# clock_module.net
KiCad netlist of a schematic drawn in Altium Designer
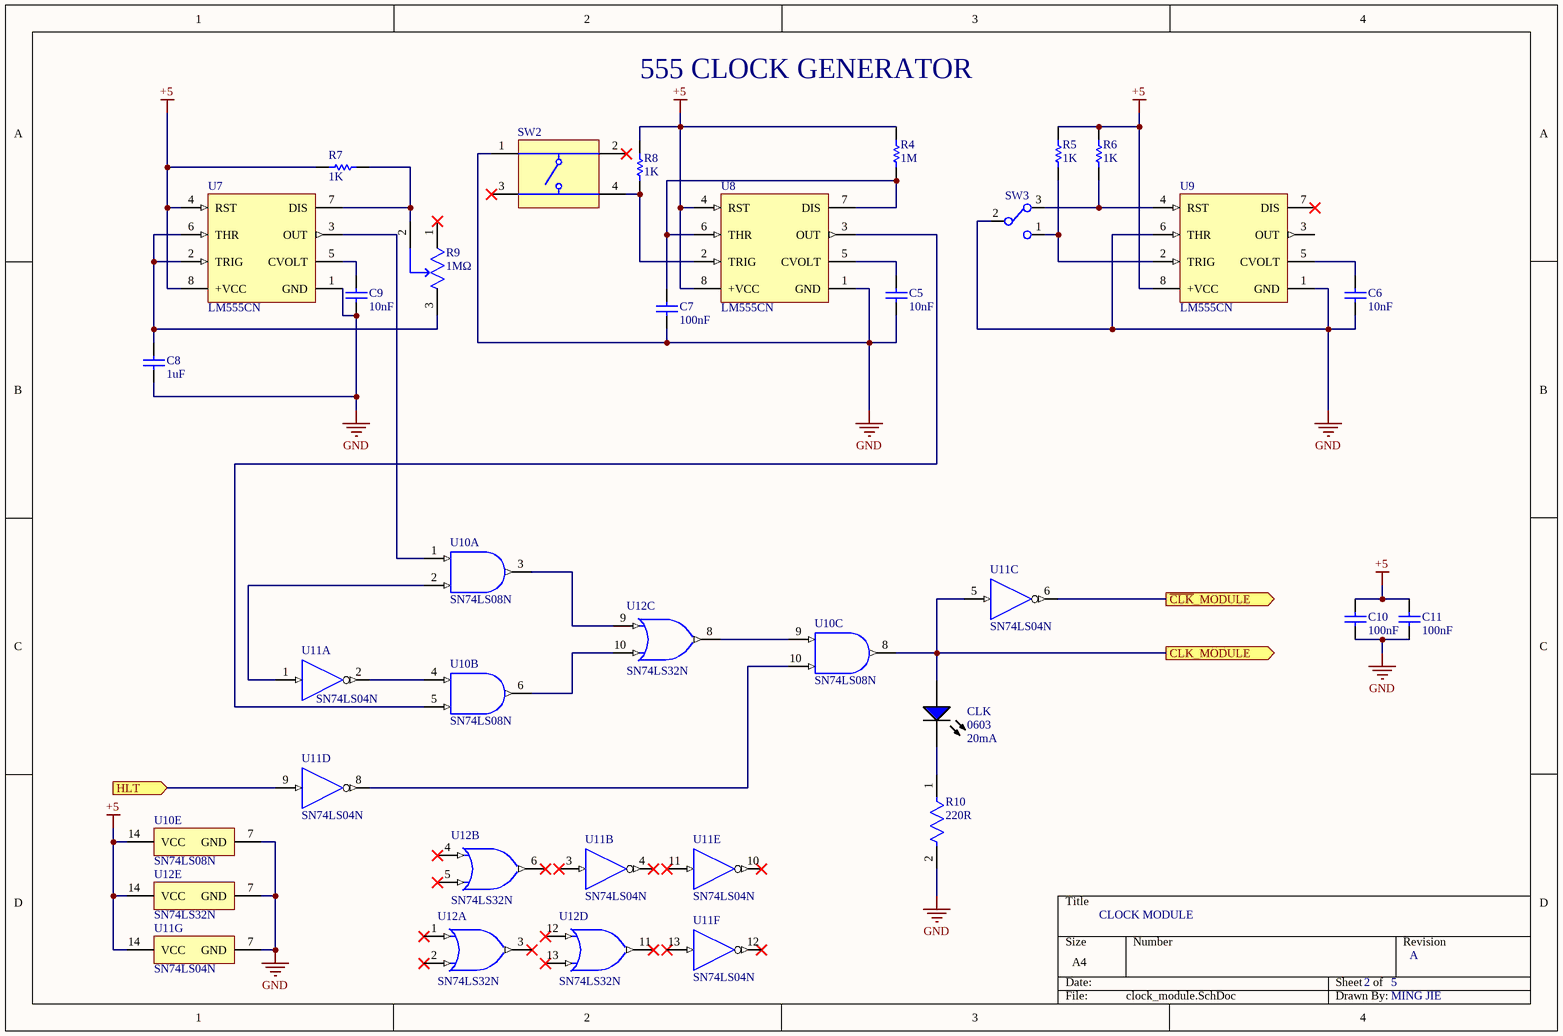
[diagram p0: clock_module.SchDoc]

(export (version "E")
  (design (tool "Eeschema 10.0.6"))
  (components
    (comp (ref "C5")
      (value "GRM216R71H103KA01D")
      (footprint "CAPC2013X70X45ML10T25")
      (description "Chip Capacitor, 10 nF, +/- 10%, 50 V, -55 to 125 degC, 0805 (2012 Metric), RoHS, Tape and Reel")
      (fields
        (field (name "CAPACITANCE") "10nF")
        (field (name "TOLERANCE") "10%")
        (field (name "MANUFACTURER") "Murata")
      )
      (libsource (lib "Altium Content Vault") (part "CAP-NP-2"))
    )
    (comp (ref "C6")
      (value "GRM216R71H103KA01D")
      (footprint "CAPC2013X70X45ML10T25")
      (description "Chip Capacitor, 10 nF, +/- 10%, 50 V, -55 to 125 degC, 0805 (2012 Metric), RoHS, Tape and Reel")
      (fields
        (field (name "CAPACITANCE") "10nF")
        (field (name "TOLERANCE") "10%")
        (field (name "MANUFACTURER") "Murata")
      )
      (libsource (lib "Altium Content Vault") (part "CAP-NP-2"))
    )
    (comp (ref "C7")
      (value "GRM21BR71H104KA01L")
      (footprint "CAPC2013X135X45ML10T25")
      (description "Chip Capacitor, 0.1 uF, +/- 10%, 50 V, -55 to 125 degC, 0805 (2012 Metric), RoHS, Tape and Reel")
      (fields
        (field (name "VOLTAGE") "50V")
        (field (name "CAPACITANCE") "100nF")
        (field (name "TOLERANCE") "10%")
      )
      (libsource (lib "Altium Content Vault") (part "CAP-NP-2"))
    )
    (comp (ref "C8")
      (value "GRM216R61E105KA12D")
      (footprint "CAPC2013X70X45NL10T25")
      (fields (field (name "MANUFACTURER") "Murata") (field (name "CAPACITANCE") "1uF"))
      (libsource (lib "Altium Content Vault") (part "CAP"))
    )
    (comp (ref "C9")
      (value "GRM216R71H103KA01D")
      (footprint "CAPC2013X70X45ML10T25")
      (description "Chip Capacitor, 10 nF, +/- 10%, 50 V, -55 to 125 degC, 0805 (2012 Metric), RoHS, Tape and Reel")
      (fields
        (field (name "CAPACITANCE") "10nF")
        (field (name "TOLERANCE") "10%")
        (field (name "MANUFACTURER") "Murata")
      )
      (libsource (lib "Altium Content Vault") (part "CAP-NP-2"))
    )
    (comp (ref "C10")
      (value "GRM21BR71H104KA01L")
      (footprint "CAPC2013X135X45ML10T25")
      (description "Chip Capacitor, 0.1 uF, +/- 10%, 50 V, -55 to 125 degC, 0805 (2012 Metric), RoHS, Tape and Reel")
      (fields
        (field (name "VOLTAGE") "50V")
        (field (name "CAPACITANCE") "100nF")
        (field (name "TOLERANCE") "10%")
      )
      (libsource (lib "Altium Content Vault") (part "CAP-NP-2"))
    )
    (comp (ref "C11")
      (value "GRM21BR71H104KA01L")
      (footprint "CAPC2013X135X45ML10T25")
      (description "Chip Capacitor, 0.1 uF, +/- 10%, 50 V, -55 to 125 degC, 0805 (2012 Metric), RoHS, Tape and Reel")
      (fields
        (field (name "VOLTAGE") "50V")
        (field (name "CAPACITANCE") "100nF")
        (field (name "TOLERANCE") "10%")
      )
      (libsource (lib "Altium Content Vault") (part "CAP-NP-2"))
    )
    (comp (ref "CLK")
      (value "19-217/BHC-ZL1M2RY/3T")
      (footprint "EVRL-0603-2_V")
      (description "Chip LED, Blue, 5 V, 25 mA, -40 to 85 degC, 2-Pin SMD (0603), RoHS, Tape and Reel")
      (fields
        (field (name "PACKAGE REFERENCE") "0603")
        (field (name "TEST CURRENT") "20mA")
        (field (name "MANUFACTURER") "Everlight Electronics")
      )
      (libsource (lib "Altium Content Vault") (part "LED-BLUE-AK-2"))
    )
    (comp (ref "R4")
      (value "CRCW08051M00JNEA")
      (footprint "RESC2013X50X30NL20T20")
      (fields (field (name "MANUFACTURER") "Vishay Dale") (field (name "RESISTANCE") "1M"))
      (libsource (lib "Altium Content Vault") (part "RES"))
    )
    (comp (ref "R5")
      (value "CRCW08051K00FKEA")
      (footprint "RESC2013X50X30NL20T20")
      (fields (field (name "MANUFACTURER") "Vishay Dale") (field (name "RESISTANCE") "1K"))
      (libsource (lib "Altium Content Vault") (part "RES"))
    )
    (comp (ref "R6")
      (value "CRCW08051K00FKEA")
      (footprint "RESC2013X50X30NL20T20")
      (fields (field (name "MANUFACTURER") "Vishay Dale") (field (name "RESISTANCE") "1K"))
      (libsource (lib "Altium Content Vault") (part "RES"))
    )
    (comp (ref "R7")
      (value "CRCW08051K00FKEA")
      (footprint "RESC2013X50X30NL20T20")
      (fields (field (name "MANUFACTURER") "Vishay Dale") (field (name "RESISTANCE") "1K"))
      (libsource (lib "Altium Content Vault") (part "RES"))
    )
    (comp (ref "R8")
      (value "CRCW08051K00FKEA")
      (footprint "RESC2013X50X30NL20T20")
      (fields (field (name "MANUFACTURER") "Vishay Dale") (field (name "RESISTANCE") "1K"))
      (libsource (lib "Altium Content Vault") (part "RES"))
    )
    (comp (ref "R9")
      (value "3296W-1-105LF")
      (footprint "FP-3296W-MFG")
      (description "TRIMMER 1M OHM 0.5W PC PIN TOP")
      (fields
        (field (name "MANUFACTURER") "Bourns")
        (field (name "RESISTANCE") "1MΩ")
        (field (name "OCTOPART") "https://octopart.com/3296w-1-504lf-bourns-143884")
      )
      (libsource (lib "Altium Content Vault") (part "8d460c8a6f7ec10b1759d1b9c49aa93"))
    )
    (comp (ref "R10")
      (value "CRCW0805220RFKEA")
      (footprint "FP-CRCW0805-e3-MFG")
      (description "RES Thick Film, 220Ω, 1%, 0.125W, 100ppm/°C, 0805")
      (fields (field (name "RESISTANCE") "220R") (field (name "TOLERANCE") "1%"))
      (libsource (lib "Altium Content Vault") (part "1029c3af85768c4190bb7ad29bc67b5"))
    )
    (comp (ref "SW2")
      (value "K2-1102SP-C4SC-04")
      (footprint "TECO-FSM4JSMA_V")
      (description "Swicth, SPST, 24 V, -35 to 85 degC, 4-Pin SMD, RoHS, Tape and Reel")
      (fields (field (name "MANUFACTURER") "TE Connectivity"))
      (libsource (lib "Altium Content Vault") (part "SW-SPST-4_A"))
    )
    (comp (ref "SW3")
      (value "SS-12D02-VG4")
      (footprint "5_2-54mm_SPDT")
      (description "SPDT, Korean Hroparts Elec SS-12D02-VG4")
      (libsource (lib "6502_lib") (part "SS-12D02-VG4"))
    )
    (comp (ref "U7")
      (value "LM555CN")
      (footprint "N08E")
      (description "Timer, 8-pin MDIP")
      (fields (field (name "MANUFACTURER") "National Semiconductor"))
      (libsource (lib "Altium Content Vault") (part "AN-TIMER-LM555-8"))
    )
    (comp (ref "U8")
      (value "LM555CN")
      (footprint "N08E")
      (description "Timer, 8-pin MDIP")
      (fields (field (name "MANUFACTURER") "National Semiconductor"))
      (libsource (lib "Altium Content Vault") (part "AN-TIMER-LM555-8"))
    )
    (comp (ref "U9")
      (value "LM555CN")
      (footprint "N08E")
      (description "Timer, 8-pin MDIP")
      (fields (field (name "MANUFACTURER") "National Semiconductor"))
      (libsource (lib "Altium Content Vault") (part "AN-TIMER-LM555-8"))
    )
    (comp (ref "U10")
      (value "SN74LS08N")
      (footprint "N0014A")
      (description "Quadruple 2-Input Positive-AND Gates, N0014A, TUBE")
      (fields
        (field (name "MANUFACTURER") "Texas Instruments")
        (field (name "GENERIC PART NUMBER") "SN74LS08")
      )
      (libsource (lib "Altium Content Vault") (part "TI-AND-4-2IN-14"))
    )
    (comp (ref "U11")
      (value "SN74LS04N")
      (footprint "N0014A")
      (description "Hex inverters, N0014A, TUBE")
      (fields
        (field (name "MANUFACTURER") "Texas Instruments")
        (field (name "GENERIC PART NUMBER") "SN74LS04")
      )
      (libsource (lib "Altium Content Vault") (part "TI-CD_SNX4XXXXXX4X_19A-14"))
    )
    (comp (ref "U12")
      (value "SN74LS32N")
      (footprint "N0014A")
      (description "Quad 2-input positive-OR gates, N0014A, TUBE")
      (fields
        (field (name "GENERIC PART NUMBER") "SN74LS32")
        (field (name "MANUFACTURER") "Texas Instruments")
      )
      (libsource (lib "Altium Content Vault") (part "TI-OR-4-2IN-14"))
    )
  )
  (nets
    (net (code "1") (name "+5") (class "Default")
      (node (ref "C10") (pin "1") (pinfunction "1_1") (pintype "passive"))
      (node (ref "C11") (pin "1") (pinfunction "1_1") (pintype "passive"))
      (node (ref "R4") (pin "1") (pinfunction "1_1") (pintype "passive"))
      (node (ref "R5") (pin "2") (pinfunction "2_2") (pintype "passive"))
      (node (ref "R6") (pin "2") (pinfunction "2_2") (pintype "passive"))
      (node (ref "R7") (pin "1") (pinfunction "1_1") (pintype "passive"))
      (node (ref "R8") (pin "2") (pinfunction "2_2") (pintype "passive"))
      (node (ref "U10") (pin "14") (pinfunction "VCC_14") (pintype "power_in"))
      (node (ref "U11") (pin "14") (pinfunction "VCC_14") (pintype "power_in"))
      (node (ref "U12") (pin "14") (pinfunction "VCC_14") (pintype "power_in"))
      (node (ref "U7") (pin "4") (pinfunction "RST_4") (pintype "input"))
      (node (ref "U7") (pin "8") (pinfunction "+VCC_8") (pintype "power_in"))
      (node (ref "U8") (pin "4") (pinfunction "RST_4") (pintype "input"))
      (node (ref "U8") (pin "8") (pinfunction "+VCC_8") (pintype "power_in"))
      (node (ref "U9") (pin "8") (pinfunction "+VCC_8") (pintype "power_in"))
    )
    (net (code "2") (name "/CLK_MODULE") (class "Default")
      (node (ref "CLK") (pin "1") (pinfunction "A_1") (pintype "passive"))
      (node (ref "U10") (pin "8") (pinfunction "3Y_8") (pintype "output"))
      (node (ref "U11") (pin "5") (pinfunction "3A_5") (pintype "input"))
    )
    (net (code "3") (name "/HLT") (class "Default")
      (node (ref "U11") (pin "9") (pinfunction "4A_9") (pintype "input"))
    )
    (net (code "4") (name "/~{CLK}_MODULE") (class "Default")
      (node (ref "U11") (pin "6") (pinfunction "~{3Y}_6") (pintype "output"))
    )
    (net (code "5") (name "GND") (class "Default")
      (node (ref "C10") (pin "2") (pinfunction "2_2") (pintype "passive"))
      (node (ref "C11") (pin "2") (pinfunction "2_2") (pintype "passive"))
      (node (ref "C5") (pin "1") (pinfunction "1_1") (pintype "passive"))
      (node (ref "C6") (pin "1") (pinfunction "1_1") (pintype "passive"))
      (node (ref "C7") (pin "2") (pinfunction "2_2") (pintype "passive"))
      (node (ref "C8") (pin "2") (pinfunction "2_2") (pintype "passive"))
      (node (ref "C9") (pin "1") (pinfunction "1_1") (pintype "passive"))
      (node (ref "R10") (pin "2") (pinfunction "2_2") (pintype "passive"))
      (node (ref "SW2") (pin "1") (pinfunction "1_1") (pintype "passive"))
      (node (ref "SW3") (pin "2") (pinfunction "2_2") (pintype "passive"))
      (node (ref "U10") (pin "7") (pinfunction "GND_7") (pintype "power_in"))
      (node (ref "U11") (pin "7") (pinfunction "GND_7") (pintype "power_in"))
      (node (ref "U12") (pin "7") (pinfunction "GND_7") (pintype "power_in"))
      (node (ref "U7") (pin "1") (pinfunction "GND_1") (pintype "power_in"))
      (node (ref "U8") (pin "1") (pinfunction "GND_1") (pintype "power_in"))
      (node (ref "U9") (pin "1") (pinfunction "GND_1") (pintype "power_in"))
      (node (ref "U9") (pin "6") (pinfunction "THR_6") (pintype "input"))
    )
    (net (code "6") (name "Net-(CLK-K)") (class "Default")
      (node (ref "CLK") (pin "2") (pinfunction "K_2") (pintype "passive"))
      (node (ref "R10") (pin "1") (pinfunction "1_1") (pintype "passive"))
    )
    (net (code "7") (name "Net-(R9-CW)") (class "Default")
      (node (ref "C8") (pin "1") (pinfunction "1_1") (pintype "passive"))
      (node (ref "R9") (pin "3") (pinfunction "CW_3") (pintype "passive"))
      (node (ref "U7") (pin "2") (pinfunction "TRIG_2") (pintype "input"))
      (node (ref "U7") (pin "6") (pinfunction "THR_6") (pintype "input"))
    )
    (net (code "8") (name "Net-(R9-WIPER)") (class "Default")
      (node (ref "R7") (pin "2") (pinfunction "2_2") (pintype "passive"))
      (node (ref "R9") (pin "2") (pinfunction "WIPER_2") (pintype "passive"))
      (node (ref "U7") (pin "7") (pinfunction "DIS_7") (pintype "open_collector"))
    )
    (net (code "9") (name "Net-(U7-CVOLT)") (class "Default")
      (node (ref "C9") (pin "2") (pinfunction "2_2") (pintype "passive"))
      (node (ref "U7") (pin "5") (pinfunction "CVOLT_5") (pintype "passive"))
    )
    (net (code "10") (name "Net-(U8-CVOLT)") (class "Default")
      (node (ref "C5") (pin "2") (pinfunction "2_2") (pintype "passive"))
      (node (ref "U8") (pin "5") (pinfunction "CVOLT_5") (pintype "passive"))
    )
    (net (code "11") (name "Net-(U8-DIS)") (class "Default")
      (node (ref "C7") (pin "1") (pinfunction "1_1") (pintype "passive"))
      (node (ref "R4") (pin "2") (pinfunction "2_2") (pintype "passive"))
      (node (ref "U8") (pin "6") (pinfunction "THR_6") (pintype "input"))
      (node (ref "U8") (pin "7") (pinfunction "DIS_7") (pintype "open_collector"))
    )
    (net (code "12") (name "Net-(U8-TRIG)") (class "Default")
      (node (ref "R8") (pin "1") (pinfunction "1_1") (pintype "passive"))
      (node (ref "SW2") (pin "4") (pinfunction "4_4") (pintype "passive"))
      (node (ref "U8") (pin "2") (pinfunction "TRIG_2") (pintype "input"))
    )
    (net (code "13") (name "Net-(U9-CVOLT)") (class "Default")
      (node (ref "C6") (pin "2") (pinfunction "2_2") (pintype "passive"))
      (node (ref "U9") (pin "5") (pinfunction "CVOLT_5") (pintype "passive"))
    )
    (net (code "14") (name "Net-(U9-RST)") (class "Default")
      (node (ref "R6") (pin "1") (pinfunction "1_1") (pintype "passive"))
      (node (ref "SW3") (pin "3") (pinfunction "3_3") (pintype "passive"))
      (node (ref "U9") (pin "4") (pinfunction "RST_4") (pintype "input"))
    )
    (net (code "15") (name "Net-(U9-TRIG)") (class "Default")
      (node (ref "R5") (pin "1") (pinfunction "1_1") (pintype "passive"))
      (node (ref "SW3") (pin "1") (pinfunction "1_1") (pintype "passive"))
      (node (ref "U9") (pin "2") (pinfunction "TRIG_2") (pintype "input"))
    )
    (net (code "16") (name "Net-(U10A-1A)") (class "Default")
      (node (ref "U10") (pin "1") (pinfunction "1A_1") (pintype "input"))
      (node (ref "U7") (pin "3") (pinfunction "OUT_3") (pintype "output"))
    )
    (net (code "17") (name "Net-(U10A-1B)") (class "Default")
      (node (ref "U10") (pin "2") (pinfunction "1B_2") (pintype "input"))
      (node (ref "U11") (pin "1") (pinfunction "1A_1") (pintype "input"))
    )
    (net (code "18") (name "Net-(U10A-1Y)") (class "Default")
      (node (ref "U10") (pin "3") (pinfunction "1Y_3") (pintype "output"))
      (node (ref "U12") (pin "9") (pinfunction "3A_9") (pintype "input"))
    )
    (net (code "19") (name "Net-(U10B-2A)") (class "Default")
      (node (ref "U10") (pin "4") (pinfunction "2A_4") (pintype "input"))
      (node (ref "U11") (pin "2") (pinfunction "~{1Y}_2") (pintype "output"))
    )
    (net (code "20") (name "Net-(U10B-2B)") (class "Default")
      (node (ref "U10") (pin "5") (pinfunction "2B_5") (pintype "input"))
      (node (ref "U8") (pin "3") (pinfunction "OUT_3") (pintype "output"))
    )
    (net (code "21") (name "Net-(U10B-2Y)") (class "Default")
      (node (ref "U10") (pin "6") (pinfunction "2Y_6") (pintype "output"))
      (node (ref "U12") (pin "10") (pinfunction "3B_10") (pintype "input"))
    )
    (net (code "22") (name "Net-(U10C-3A)") (class "Default")
      (node (ref "U10") (pin "9") (pinfunction "3A_9") (pintype "input"))
      (node (ref "U12") (pin "8") (pinfunction "3Y_8") (pintype "output"))
    )
    (net (code "23") (name "Net-(U10C-3B)") (class "Default")
      (node (ref "U10") (pin "10") (pinfunction "3B_10") (pintype "input"))
      (node (ref "U11") (pin "8") (pinfunction "~{4Y}_8") (pintype "output"))
    )
    (net (code "24") (name "unconnected-(R9-CCW-Pad1)") (class "Default")
      (node (ref "R9") (pin "1") (pinfunction "CCW_1") (pintype "passive+no_connect"))
    )
    (net (code "25") (name "unconnected-(SW2-Pad2)") (class "Default")
      (node (ref "SW2") (pin "2") (pinfunction "2_2") (pintype "passive+no_connect"))
    )
    (net (code "26") (name "unconnected-(SW2-Pad3)") (class "Default")
      (node (ref "SW2") (pin "3") (pinfunction "3_3") (pintype "passive+no_connect"))
    )
    (net (code "27") (name "unconnected-(U9-DIS-Pad7)") (class "Default")
      (node (ref "U9") (pin "7") (pinfunction "DIS_7") (pintype "open_collector+no_connect"))
    )
    (net (code "28") (name "unconnected-(U9-OUT-Pad3)") (class "Default")
      (node (ref "U9") (pin "3") (pinfunction "OUT_3") (pintype "output"))
    )
    (net (code "29") (name "unconnected-(U11B-2A-Pad3)") (class "Default")
      (node (ref "U11") (pin "3") (pinfunction "2A_3") (pintype "input+no_connect"))
    )
    (net (code "30") (name "unconnected-(U11B-~{2Y}-Pad4)") (class "Default")
      (node (ref "U11") (pin "4") (pinfunction "~{2Y}_4") (pintype "output+no_connect"))
    )
    (net (code "31") (name "unconnected-(U11E-5A-Pad11)") (class "Default")
      (node (ref "U11") (pin "11") (pinfunction "5A_11") (pintype "input+no_connect"))
    )
    (net (code "32") (name "unconnected-(U11E-~{5Y}-Pad10)") (class "Default")
      (node (ref "U11") (pin "10") (pinfunction "~{5Y}_10") (pintype "output+no_connect"))
    )
    (net (code "33") (name "unconnected-(U11F-6A-Pad13)") (class "Default")
      (node (ref "U11") (pin "13") (pinfunction "6A_13") (pintype "input+no_connect"))
    )
    (net (code "34") (name "unconnected-(U11F-~{6Y}-Pad12)") (class "Default")
      (node (ref "U11") (pin "12") (pinfunction "~{6Y}_12") (pintype "output+no_connect"))
    )
    (net (code "35") (name "unconnected-(U12A-1A-Pad1)") (class "Default")
      (node (ref "U12") (pin "1") (pinfunction "1A_1") (pintype "input+no_connect"))
    )
    (net (code "36") (name "unconnected-(U12A-1B-Pad2)") (class "Default")
      (node (ref "U12") (pin "2") (pinfunction "1B_2") (pintype "input+no_connect"))
    )
    (net (code "37") (name "unconnected-(U12A-1Y-Pad3)") (class "Default")
      (node (ref "U12") (pin "3") (pinfunction "1Y_3") (pintype "output+no_connect"))
    )
    (net (code "38") (name "unconnected-(U12B-2A-Pad4)") (class "Default")
      (node (ref "U12") (pin "4") (pinfunction "2A_4") (pintype "input+no_connect"))
    )
    (net (code "39") (name "unconnected-(U12B-2B-Pad5)") (class "Default")
      (node (ref "U12") (pin "5") (pinfunction "2B_5") (pintype "input+no_connect"))
    )
    (net (code "40") (name "unconnected-(U12B-2Y-Pad6)") (class "Default")
      (node (ref "U12") (pin "6") (pinfunction "2Y_6") (pintype "output+no_connect"))
    )
    (net (code "41") (name "unconnected-(U12D-4A-Pad12)") (class "Default")
      (node (ref "U12") (pin "12") (pinfunction "4A_12") (pintype "input+no_connect"))
    )
    (net (code "42") (name "unconnected-(U12D-4B-Pad13)") (class "Default")
      (node (ref "U12") (pin "13") (pinfunction "4B_13") (pintype "input+no_connect"))
    )
    (net (code "43") (name "unconnected-(U12D-4Y-Pad11)") (class "Default")
      (node (ref "U12") (pin "11") (pinfunction "4Y_11") (pintype "output+no_connect"))
    )
  )
)
